# Main.net
KiCad netlist of a schematic drawn in Altium Designer
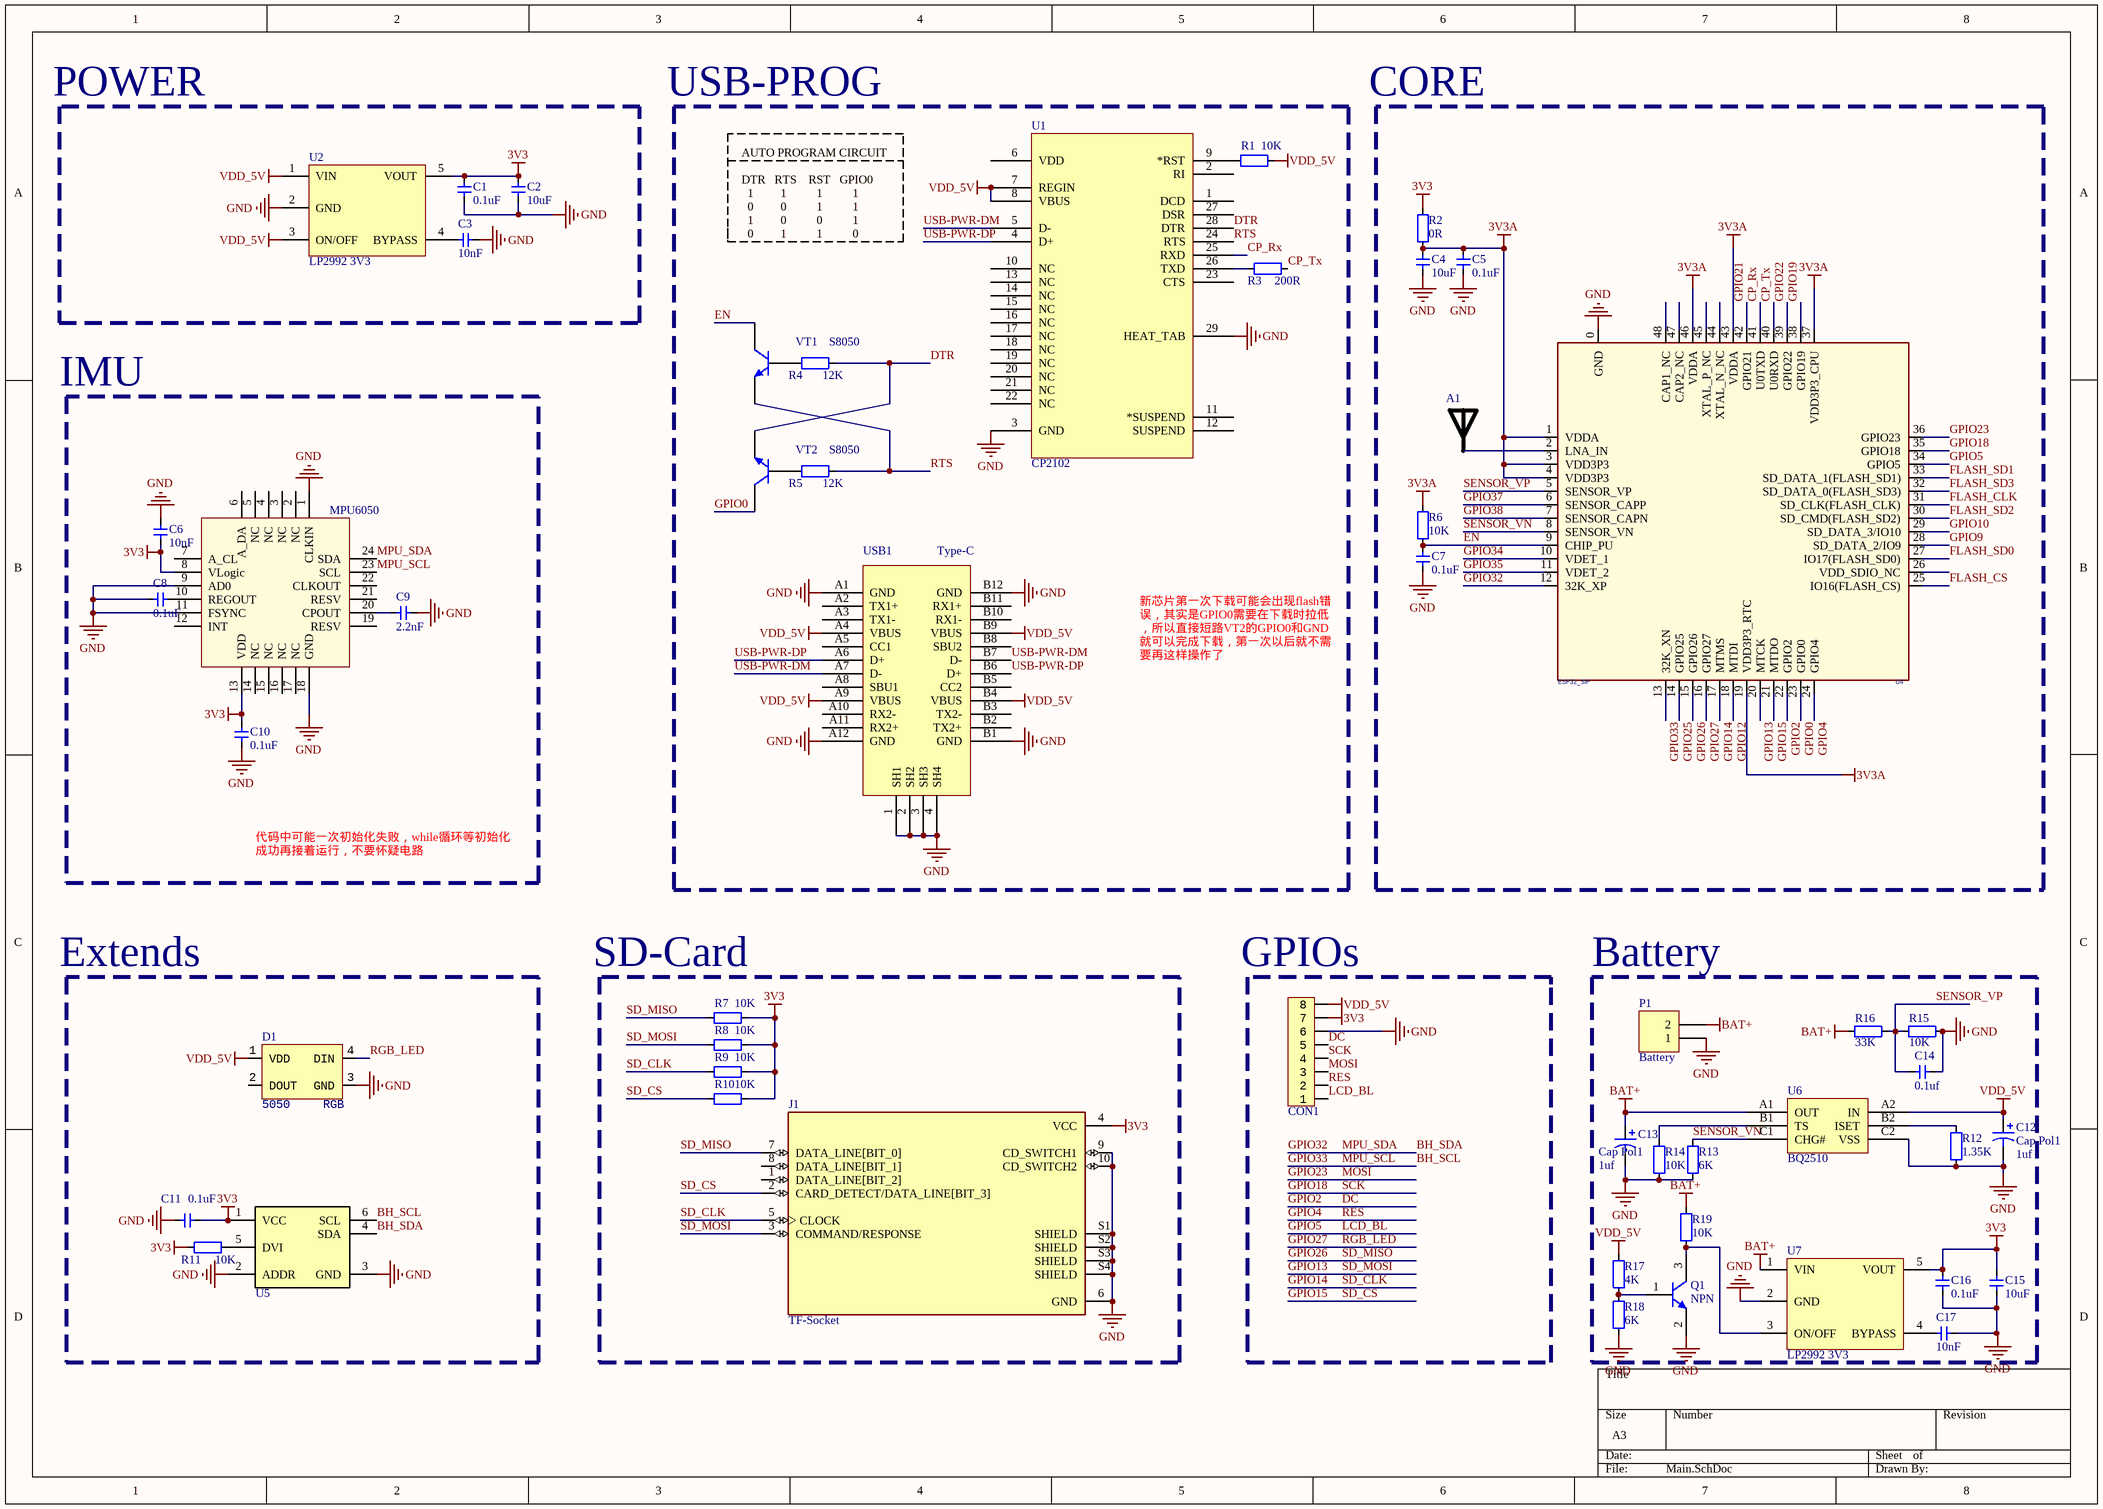
[diagram p0: Main.SchDoc]

(export (version "E")
  (design (tool "Eeschema 10.0.6"))
  (components
    (comp (ref "A1")
      (value "RAINSUN")
      (footprint "ANT-Rainsun-AN5120")
      (libsource (lib "MyPcbLib") (part "ANT-Rainsun-AP5120"))
    )
    (comp (ref "C1")
      (value "0.1uF")
      (footprint "CAP_0402")
      (description "Capacitor")
      (libsource (lib "MyPcbLib") (part "电容-0402"))
    )
    (comp (ref "C2")
      (value "10uF")
      (footprint "CAP_0402")
      (description "Capacitor")
      (libsource (lib "MyPcbLib") (part "电容-0402"))
    )
    (comp (ref "C3")
      (value "10nF")
      (footprint "CAP_0402")
      (description "Capacitor")
      (libsource (lib "MyPcbLib") (part "电容-0402"))
    )
    (comp (ref "C4")
      (value "10uF")
      (footprint "CAP_0402")
      (description "Capacitor")
      (libsource (lib "MyPcbLib") (part "电容-0402"))
    )
    (comp (ref "C5")
      (value "0.1uF")
      (footprint "CAP_0402")
      (description "Capacitor")
      (libsource (lib "MyPcbLib") (part "电容-0402"))
    )
    (comp (ref "C6")
      (value "10nF")
      (footprint "CAP_0402")
      (description "Capacitor")
      (libsource (lib "MyPcbLib") (part "电容-0402"))
    )
    (comp (ref "C7")
      (value "0.1uF")
      (footprint "CAP_0402")
      (description "Capacitor")
      (libsource (lib "MyPcbLib") (part "电容-0402"))
    )
    (comp (ref "C8")
      (value "0.1uF")
      (footprint "CAP_0402")
      (description "Capacitor")
      (libsource (lib "MyPcbLib") (part "电容-0402"))
    )
    (comp (ref "C9")
      (value "2.2nF")
      (footprint "CAP_0402")
      (description "Capacitor")
      (libsource (lib "MyPcbLib") (part "电容-0402"))
    )
    (comp (ref "C10")
      (value "0.1uF")
      (footprint "CAP_0402")
      (description "Capacitor")
      (libsource (lib "MyPcbLib") (part "电容-0402"))
    )
    (comp (ref "C11")
      (value "0.1uF")
      (footprint "CAP_0402")
      (description "Capacitor")
      (libsource (lib "MyPcbLib") (part "电容-0402"))
    )
    (comp (ref "C12")
      (value "Cap Pol1")
      (footprint "6-0805_L")
      (description "Polarized Capacitor (Radial)")
      (fields (field (name "ALTIUM_VALUE") "1uf") (field (name "PUBLISHER") "Altium Limited"))
      (libsource (lib "Miscellaneous Devices") (part "Cap Pol1"))
    )
    (comp (ref "C13")
      (value "Cap Pol1")
      (footprint "6-0805_L")
      (description "Polarized Capacitor (Radial)")
      (fields (field (name "ALTIUM_VALUE") "1uf") (field (name "PUBLISHER") "Altium Limited"))
      (libsource (lib "Miscellaneous Devices") (part "Cap Pol1"))
    )
    (comp (ref "C14")
      (value "0.1uf")
      (footprint "CAP_0402")
      (description "Capacitor")
      (libsource (lib "MyPcbLib") (part "电容-0402"))
    )
    (comp (ref "C15")
      (value "10uF")
      (footprint "CAP_0402")
      (description "Capacitor")
      (libsource (lib "MyPcbLib") (part "电容-0402"))
    )
    (comp (ref "C16")
      (value "0.1uF")
      (footprint "CAP_0402")
      (description "Capacitor")
      (libsource (lib "MyPcbLib") (part "电容-0402"))
    )
    (comp (ref "C17")
      (value "10nF")
      (footprint "CAP_0402")
      (description "Capacitor")
      (libsource (lib "MyPcbLib") (part "电容-0402"))
    )
    (comp (ref "CON1")
      (value "FFC_0.5_8")
      (footprint "FFC_0.5_8")
      (description "FFC")
      (libsource (lib "KitSprout") (part "FFC_0.5_8"))
    )
    (comp (ref "D1")
      (value "RGB")
      (footprint "LED_5050_WS2812B")
      (description "LED")
      (fields (field (name "TYPE") "5050"))
      (libsource (lib "KitSprout") (part "LED_5050_WS2812B"))
    )
    (comp (ref "J1")
      (value "TF-Socket")
      (footprint "TF-Card-Amphenol with TF")
      (description "10 _8 + 2_ Position Card Connector Secure Digital - microSDâ„¢ Surface Mount, Right Angle Gold")
      (fields (field (name "MP") "1140084168") (field (name "MF") "Amphenol Commercial Products"))
      (libsource (lib "MyPcbLib") (part "TF-Socket"))
    )
    (comp (ref "P1")
      (value "Battery")
      (footprint "C0805")
      (description "Header, 2-Pin")
      (fields (field (name "PUBLISHER") "Altium Limited"))
      (libsource (lib "Miscellaneous Connectors") (part "Header 2"))
    )
    (comp (ref "Q1")
      (value "NPN")
      (footprint "SOT-23_N")
      (description "NPN Bipolar Transistor")
      (fields (field (name "PUBLISHER") "Altium Limited"))
      (libsource (lib "Miscellaneous Devices") (part "NPN"))
    )
    (comp (ref "R1")
      (value "10K")
      (footprint "RES_0402")
      (description "Resistor")
      (libsource (lib "") (part "电阻-0402_1"))
    )
    (comp (ref "R2")
      (value "0R")
      (footprint "RES_0402")
      (description "Resistor")
      (libsource (lib "MyPcbLib") (part "电阻-0402"))
    )
    (comp (ref "R3")
      (value "200R")
      (footprint "RES_0402")
      (description "Resistor")
      (libsource (lib "") (part "电阻-0402_1"))
    )
    (comp (ref "R4")
      (value "12K")
      (footprint "RES_0402")
      (description "Resistor")
      (libsource (lib "") (part "电阻-0402_1"))
    )
    (comp (ref "R5")
      (value "12K")
      (footprint "RES_0402")
      (description "Resistor")
      (libsource (lib "") (part "电阻-0402_1"))
    )
    (comp (ref "R6")
      (value "10K")
      (footprint "RES_0402")
      (description "Resistor")
      (libsource (lib "MyPcbLib") (part "电阻-0402"))
    )
    (comp (ref "R7")
      (value "10K")
      (footprint "RES_0402")
      (description "Resistor")
      (libsource (lib "") (part "电阻-0402_1"))
    )
    (comp (ref "R8")
      (value "10K")
      (footprint "RES_0402")
      (description "Resistor")
      (libsource (lib "") (part "电阻-0402_1"))
    )
    (comp (ref "R9")
      (value "10K")
      (footprint "RES_0402")
      (description "Resistor")
      (libsource (lib "") (part "电阻-0402_1"))
    )
    (comp (ref "R10")
      (value "10K")
      (footprint "RES_0402")
      (description "Resistor")
      (libsource (lib "") (part "电阻-0402_1"))
    )
    (comp (ref "R11")
      (value "10K")
      (footprint "RES_0402")
      (description "Resistor")
      (libsource (lib "") (part "电阻-0402_1"))
    )
    (comp (ref "R12")
      (value "1.35K")
      (footprint "RES_0402")
      (description "Resistor")
      (libsource (lib "MyPcbLib") (part "电阻-0402"))
    )
    (comp (ref "R13")
      (value "6K")
      (footprint "RES_0402")
      (description "Resistor")
      (libsource (lib "MyPcbLib") (part "电阻-0402"))
    )
    (comp (ref "R14")
      (value "10K")
      (footprint "RES_0402")
      (description "Resistor")
      (libsource (lib "MyPcbLib") (part "电阻-0402"))
    )
    (comp (ref "R15")
      (value "10K")
      (footprint "RES_0402")
      (description "Resistor")
      (libsource (lib "") (part "电阻-0402_2"))
    )
    (comp (ref "R16")
      (value "33K")
      (footprint "RES_0402")
      (description "Resistor")
      (libsource (lib "") (part "电阻-0402_2"))
    )
    (comp (ref "R17")
      (value "4K")
      (footprint "RES_0402")
      (description "Resistor")
      (libsource (lib "MyPcbLib") (part "电阻-0402"))
    )
    (comp (ref "R18")
      (value "6K")
      (footprint "RES_0402")
      (description "Resistor")
      (libsource (lib "MyPcbLib") (part "电阻-0402"))
    )
    (comp (ref "R19")
      (value "10K")
      (footprint "RES_0402")
      (description "Resistor")
      (libsource (lib "MyPcbLib") (part "电阻-0402"))
    )
    (comp (ref "U1")
      (value "CP2102")
      (footprint "QFN-28")
      (description "USB转TTL")
      (libsource (lib "mLib") (part "CP2102"))
    )
    (comp (ref "U2")
      (value "LP2992 3V3")
      (footprint "SOT23-5")
      (description "LDO")
      (libsource (lib "MyPcbLib") (part "LP2992"))
    )
    (comp (ref "U3")
      (value "MPU6050")
      (footprint "QFN-24")
      (description "六轴传感器")
      (libsource (lib "mLib") (part "MPU6050"))
    )
    (comp (ref "U4")
      (value "ESP32_SIP")
      (footprint "QFN-48_7X7")
      (libsource (lib "MyPcbLib") (part "ESP32-PICO"))
    )
    (comp (ref "U5")
      (value "BH1750FVI-TR")
      (footprint "BH1750FVI")
      (libsource (lib "MyPcbLib") (part "BH1750FVI-TR"))
    )
    (comp (ref "U6")
      (value "BQ2510")
      (footprint "BQ2510")
      (libsource (lib "Integrated_Library1") (part "BQ2510"))
    )
    (comp (ref "U7")
      (value "LP2992 3V3")
      (footprint "SOT23-5")
      (description "LDO")
      (libsource (lib "MyPcbLib") (part "LP2992"))
    )
    (comp (ref "USB1")
      (value "Type-C")
      (footprint "Type-C-TOP")
      (libsource (lib "MyPcbLib") (part "USB-Type-C-TOP"))
    )
    (comp (ref "VT1")
      (value "S8050")
      (footprint "SMT_TRIODE_NPN")
      (description "Surface mount NPN transistor, package SOT-23")
      (libsource (lib "MyPcbLib") (part "SMT_TRIODE_NPN"))
    )
    (comp (ref "VT2")
      (value "S8050")
      (footprint "SMT_TRIODE_NPN")
      (description "Surface mount NPN transistor, package SOT-23")
      (libsource (lib "MyPcbLib") (part "SMT_TRIODE_NPN"))
    )
  )
  (nets
    (net (code "1") (name "/BH_SCL") (class "Default")
      (node (ref "U3") (pin "23") (pinfunction "SCL_23") (pintype "passive"))
      (node (ref "U4") (pin "13") (pinfunction "32K_XN_13") (pintype "passive"))
      (node (ref "U5") (pin "6") (pinfunction "SCL_6") (pintype "passive"))
    )
    (net (code "2") (name "/BH_SDA") (class "Default")
      (node (ref "U3") (pin "24") (pinfunction "SDA_24") (pintype "passive"))
      (node (ref "U4") (pin "12") (pinfunction "32K_XP_12") (pintype "passive"))
      (node (ref "U5") (pin "4") (pinfunction "SDA_4") (pintype "passive"))
    )
    (net (code "3") (name "/CP_Rx") (class "Default")
      (node (ref "U1") (pin "25") (pinfunction "RXD_25") (pintype "passive"))
      (node (ref "U4") (pin "41") (pinfunction "U0TXD_41") (pintype "power_in"))
    )
    (net (code "4") (name "/CP_Tx") (class "Default")
      (node (ref "R3") (pin "1") (pinfunction "1_1") (pintype "passive"))
      (node (ref "U4") (pin "40") (pinfunction "U0RXD_40") (pintype "power_in"))
    )
    (net (code "5") (name "/DC") (class "Default")
      (node (ref "CON1") (pin "5") (pinfunction "5_5") (pintype "passive"))
      (node (ref "U4") (pin "22") (pinfunction "GPIO2_22") (pintype "passive"))
    )
    (net (code "6") (name "/DTR") (class "Default")
      (node (ref "R4") (pin "1") (pinfunction "1_1") (pintype "passive"))
      (node (ref "U1") (pin "28") (pinfunction "DTR_28") (pintype "passive"))
      (node (ref "VT2") (pin "2") (pinfunction "E_2") (pintype "passive"))
    )
    (net (code "7") (name "/EN") (class "Default")
      (node (ref "C7") (pin "1") (pinfunction "1_1") (pintype "passive"))
      (node (ref "R6") (pin "2") (pinfunction "2_2") (pintype "passive"))
      (node (ref "U4") (pin "9") (pinfunction "CHIP_PU_9") (pintype "passive"))
      (node (ref "VT1") (pin "3") (pinfunction "C_3") (pintype "passive"))
    )
    (net (code "8") (name "/FLASH_CLK") (class "Default")
      (node (ref "U4") (pin "31") (pinfunction "SD_CLK(FLASH_CLK)_31") (pintype "passive"))
    )
    (net (code "9") (name "/FLASH_CS") (class "Default")
      (node (ref "U4") (pin "25") (pinfunction "IO16(FLASH_CS)_25") (pintype "passive"))
    )
    (net (code "10") (name "/FLASH_SD0") (class "Default")
      (node (ref "U4") (pin "27") (pinfunction "IO17(FLASH_SD0)_27") (pintype "passive"))
    )
    (net (code "11") (name "/FLASH_SD1") (class "Default")
      (node (ref "U4") (pin "33") (pinfunction "SD_DATA_1(FLASH_SD1)_33") (pintype "passive"))
    )
    (net (code "12") (name "/FLASH_SD2") (class "Default")
      (node (ref "U4") (pin "30") (pinfunction "SD_CMD(FLASH_SD2)_30") (pintype "passive"))
    )
    (net (code "13") (name "/FLASH_SD3") (class "Default")
      (node (ref "U4") (pin "32") (pinfunction "SD_DATA_0(FLASH_SD3)_32") (pintype "passive"))
    )
    (net (code "14") (name "/GPIO0") (class "Default")
      (node (ref "U4") (pin "23") (pinfunction "GPIO0_23") (pintype "passive"))
      (node (ref "VT2") (pin "3") (pinfunction "C_3") (pintype "passive"))
    )
    (net (code "15") (name "/GPIO4") (class "Default")
      (node (ref "CON1") (pin "2") (pinfunction "2_2") (pintype "passive"))
      (node (ref "U4") (pin "24") (pinfunction "GPIO4_24") (pintype "passive"))
    )
    (net (code "16") (name "/GPIO5") (class "Default")
      (node (ref "CON1") (pin "1") (pinfunction "1_1") (pintype "passive"))
      (node (ref "U4") (pin "34") (pinfunction "GPIO5_34") (pintype "passive"))
    )
    (net (code "17") (name "/GPIO9") (class "Default")
      (node (ref "U4") (pin "28") (pinfunction "SD_DATA_2/IO9_28") (pintype "passive"))
    )
    (net (code "18") (name "/GPIO10") (class "Default")
      (node (ref "U4") (pin "29") (pinfunction "SD_DATA_3/IO10_29") (pintype "passive"))
    )
    (net (code "19") (name "/GPIO12") (class "Default")
      (node (ref "U4") (pin "18") (pinfunction "MTDI_18") (pintype "passive"))
    )
    (net (code "20") (name "/GPIO13") (class "Default")
      (node (ref "J1") (pin "3") (pinfunction "COMMAND/RESPONSE_3") (pintype "bidirectional"))
      (node (ref "R8") (pin "2") (pinfunction "2_2") (pintype "passive"))
      (node (ref "U4") (pin "20") (pinfunction "MTCK_20") (pintype "passive"))
    )
    (net (code "21") (name "/GPIO14") (class "Default")
      (node (ref "J1") (pin "5") (pinfunction "CLOCK_5") (pintype "bidirectional"))
      (node (ref "R9") (pin "2") (pinfunction "2_2") (pintype "passive"))
      (node (ref "U4") (pin "17") (pinfunction "MTMS_17") (pintype "passive"))
    )
    (net (code "22") (name "/GPIO15") (class "Default")
      (node (ref "J1") (pin "2") (pinfunction "CARD_DETECT/DATA_LINE[BIT_3]_2") (pintype "bidirectional"))
      (node (ref "R10") (pin "2") (pinfunction "2_2") (pintype "passive"))
      (node (ref "U4") (pin "21") (pinfunction "MTDO_21") (pintype "passive"))
    )
    (net (code "23") (name "/GPIO18") (class "Default")
      (node (ref "CON1") (pin "4") (pinfunction "4_4") (pintype "passive"))
      (node (ref "U4") (pin "35") (pinfunction "GPIO18_35") (pintype "passive"))
    )
    (net (code "24") (name "/GPIO19") (class "Default")
      (node (ref "U4") (pin "38") (pinfunction "GPIO19_38") (pintype "passive"))
    )
    (net (code "25") (name "/GPIO21") (class "Default")
      (node (ref "U4") (pin "42") (pinfunction "GPIO21_42") (pintype "passive"))
    )
    (net (code "26") (name "/GPIO22") (class "Default")
      (node (ref "U4") (pin "39") (pinfunction "GPIO22_39") (pintype "passive"))
    )
    (net (code "27") (name "/GPIO23") (class "Default")
      (node (ref "CON1") (pin "3") (pinfunction "3_3") (pintype "passive"))
      (node (ref "U4") (pin "36") (pinfunction "GPIO23_36") (pintype "passive"))
    )
    (net (code "28") (name "/GPIO25") (class "Default")
      (node (ref "U4") (pin "14") (pinfunction "GPIO25_14") (pintype "passive"))
    )
    (net (code "29") (name "/GPIO26") (class "Default")
      (node (ref "J1") (pin "7") (pinfunction "DATA_LINE[BIT_0]_7") (pintype "bidirectional"))
      (node (ref "R7") (pin "2") (pinfunction "2_2") (pintype "passive"))
      (node (ref "U4") (pin "15") (pinfunction "GPIO26_15") (pintype "passive"))
    )
    (net (code "30") (name "/GPIO27") (class "Default")
      (node (ref "D1") (pin "4") (pinfunction "DIN_4") (pintype "passive"))
      (node (ref "U4") (pin "16") (pinfunction "GPIO27_16") (pintype "passive"))
    )
    (net (code "31") (name "/GPIO34") (class "Default")
      (node (ref "U4") (pin "10") (pinfunction "VDET_1_10") (pintype "passive"))
    )
    (net (code "32") (name "/GPIO35") (class "Default")
      (node (ref "U4") (pin "11") (pinfunction "VDET_2_11") (pintype "passive"))
    )
    (net (code "33") (name "/GPIO37") (class "Default")
      (node (ref "U4") (pin "6") (pinfunction "SENSOR_CAPP_6") (pintype "passive"))
    )
    (net (code "34") (name "/GPIO38") (class "Default")
      (node (ref "U4") (pin "7") (pinfunction "SENSOR_CAPN_7") (pintype "passive"))
    )
    (net (code "35") (name "/RTS") (class "Default")
      (node (ref "R5") (pin "1") (pinfunction "1_1") (pintype "passive"))
      (node (ref "U1") (pin "24") (pinfunction "RTS_24") (pintype "passive"))
      (node (ref "VT1") (pin "2") (pinfunction "E_2") (pintype "passive"))
    )
    (net (code "36") (name "/SENSOR_VN") (class "Default")
      (node (ref "R13") (pin "1") (pinfunction "1_1") (pintype "passive"))
      (node (ref "U4") (pin "8") (pinfunction "SENSOR_VN_8") (pintype "passive"))
      (node (ref "U6") (pin "C1") (pinfunction "CHG#_C1") (pintype "passive"))
    )
    (net (code "37") (name "/SENSOR_VP") (class "Default")
      (node (ref "C14") (pin "2") (pinfunction "2_2") (pintype "passive"))
      (node (ref "R15") (pin "1") (pinfunction "1_1") (pintype "passive"))
      (node (ref "R16") (pin "2") (pinfunction "2_2") (pintype "passive"))
      (node (ref "U4") (pin "5") (pinfunction "SENSOR_VP_5") (pintype "passive"))
    )
    (net (code "38") (name "/USB-PWR-DM") (class "Default")
      (node (ref "U1") (pin "5") (pinfunction "D-_5") (pintype "passive"))
      (node (ref "USB1") (pin "A7") (pinfunction "D-_A7") (pintype "passive"))
      (node (ref "USB1") (pin "B7") (pinfunction "D-_B7") (pintype "passive"))
    )
    (net (code "39") (name "/USB-PWR-DP") (class "Default")
      (node (ref "U1") (pin "4") (pinfunction "D+_4") (pintype "passive"))
      (node (ref "USB1") (pin "A6") (pinfunction "D+_A6") (pintype "passive"))
      (node (ref "USB1") (pin "B6") (pinfunction "D+_B6") (pintype "passive"))
    )
    (net (code "40") (name "3V3") (class "Default")
      (node (ref "C1") (pin "2") (pinfunction "2_2") (pintype "passive"))
      (node (ref "C10") (pin "2") (pinfunction "2_2") (pintype "passive"))
      (node (ref "C11") (pin "1") (pinfunction "1_1") (pintype "passive"))
      (node (ref "C15") (pin "2") (pinfunction "2_2") (pintype "passive"))
      (node (ref "C16") (pin "2") (pinfunction "2_2") (pintype "passive"))
      (node (ref "C2") (pin "2") (pinfunction "2_2") (pintype "passive"))
      (node (ref "C6") (pin "1") (pinfunction "1_1") (pintype "passive"))
      (node (ref "CON1") (pin "7") (pinfunction "7_7") (pintype "passive"))
      (node (ref "J1") (pin "4") (pinfunction "VCC_4") (pintype "power_in"))
      (node (ref "R10") (pin "1") (pinfunction "1_1") (pintype "passive"))
      (node (ref "R11") (pin "2") (pinfunction "2_2") (pintype "passive"))
      (node (ref "R2") (pin "1") (pinfunction "1_1") (pintype "passive"))
      (node (ref "R7") (pin "1") (pinfunction "1_1") (pintype "passive"))
      (node (ref "R8") (pin "1") (pinfunction "1_1") (pintype "passive"))
      (node (ref "R9") (pin "1") (pinfunction "1_1") (pintype "passive"))
      (node (ref "U2") (pin "5") (pinfunction "VOUT_5") (pintype "passive"))
      (node (ref "U3") (pin "13") (pinfunction "VDD_13") (pintype "passive"))
      (node (ref "U3") (pin "8") (pinfunction "VLogic_8") (pintype "passive"))
      (node (ref "U5") (pin "1") (pinfunction "VCC_1") (pintype "passive"))
      (node (ref "U7") (pin "5") (pinfunction "VOUT_5") (pintype "passive"))
    )
    (net (code "41") (name "3V3A") (class "Default")
      (node (ref "C4") (pin "2") (pinfunction "2_2") (pintype "passive"))
      (node (ref "C5") (pin "2") (pinfunction "2_2") (pintype "passive"))
      (node (ref "R2") (pin "2") (pinfunction "2_2") (pintype "passive"))
      (node (ref "R6") (pin "1") (pinfunction "1_1") (pintype "passive"))
      (node (ref "U4") (pin "1") (pinfunction "VDDA_1") (pintype "power_in"))
      (node (ref "U4") (pin "19") (pinfunction "VDD3P3_RTC_19") (pintype "power_in"))
      (node (ref "U4") (pin "3") (pinfunction "VDD3P3_3") (pintype "power_in"))
      (node (ref "U4") (pin "37") (pinfunction "VDD3P3_CPU_37") (pintype "power_in"))
      (node (ref "U4") (pin "4") (pinfunction "VDD3P3_4") (pintype "power_in"))
      (node (ref "U4") (pin "43") (pinfunction "VDDA_43") (pintype "power_in"))
      (node (ref "U4") (pin "46") (pinfunction "VDDA_46") (pintype "power_in"))
    )
    (net (code "42") (name "BAT+") (class "Default")
      (node (ref "C13") (pin "1") (pinfunction "1_1") (pintype "passive"))
      (node (ref "P1") (pin "2") (pinfunction "2_2") (pintype "passive"))
      (node (ref "R16") (pin "1") (pinfunction "1_1") (pintype "passive"))
      (node (ref "R19") (pin "1") (pinfunction "1_1") (pintype "passive"))
      (node (ref "U6") (pin "A1") (pinfunction "OUT_A1") (pintype "passive"))
      (node (ref "U7") (pin "1") (pinfunction "VIN_1") (pintype "passive"))
    )
    (net (code "43") (name "GND") (class "Default")
      (node (ref "C1") (pin "1") (pinfunction "1_1") (pintype "passive"))
      (node (ref "C10") (pin "1") (pinfunction "1_1") (pintype "passive"))
      (node (ref "C11") (pin "2") (pinfunction "2_2") (pintype "passive"))
      (node (ref "C12") (pin "2") (pinfunction "2_2") (pintype "passive"))
      (node (ref "C13") (pin "2") (pinfunction "2_2") (pintype "passive"))
      (node (ref "C14") (pin "1") (pinfunction "1_1") (pintype "passive"))
      (node (ref "C15") (pin "1") (pinfunction "1_1") (pintype "passive"))
      (node (ref "C16") (pin "1") (pinfunction "1_1") (pintype "passive"))
      (node (ref "C17") (pin "1") (pinfunction "1_1") (pintype "passive"))
      (node (ref "C2") (pin "1") (pinfunction "1_1") (pintype "passive"))
      (node (ref "C3") (pin "1") (pinfunction "1_1") (pintype "passive"))
      (node (ref "C4") (pin "1") (pinfunction "1_1") (pintype "passive"))
      (node (ref "C5") (pin "1") (pinfunction "1_1") (pintype "passive"))
      (node (ref "C6") (pin "2") (pinfunction "2_2") (pintype "passive"))
      (node (ref "C7") (pin "2") (pinfunction "2_2") (pintype "passive"))
      (node (ref "C8") (pin "2") (pinfunction "2_2") (pintype "passive"))
      (node (ref "C9") (pin "1") (pinfunction "1_1") (pintype "passive"))
      (node (ref "CON1") (pin "6") (pinfunction "6_6") (pintype "passive"))
      (node (ref "D1") (pin "3") (pinfunction "GND_3") (pintype "passive"))
      (node (ref "J1") (pin "10") (pinfunction "CD_SWITCH2_10") (pintype "bidirectional"))
      (node (ref "J1") (pin "6") (pinfunction "GND_6") (pintype "power_in"))
      (node (ref "J1") (pin "9") (pinfunction "CD_SWITCH1_9") (pintype "bidirectional"))
      (node (ref "J1") (pin "S1") (pinfunction "SHIELD_S1") (pintype "passive"))
      (node (ref "J1") (pin "S2") (pinfunction "SHIELD_S2") (pintype "passive"))
      (node (ref "J1") (pin "S3") (pinfunction "SHIELD_S3") (pintype "passive"))
      (node (ref "J1") (pin "S4") (pinfunction "SHIELD_S4") (pintype "passive"))
      (node (ref "P1") (pin "1") (pinfunction "1_1") (pintype "passive"))
      (node (ref "Q1") (pin "2") (pinfunction "E_2") (pintype "passive"))
      (node (ref "R12") (pin "2") (pinfunction "2_2") (pintype "passive"))
      (node (ref "R13") (pin "2") (pinfunction "2_2") (pintype "passive"))
      (node (ref "R14") (pin "2") (pinfunction "2_2") (pintype "passive"))
      (node (ref "R15") (pin "2") (pinfunction "2_2") (pintype "passive"))
      (node (ref "R18") (pin "2") (pinfunction "2_2") (pintype "passive"))
      (node (ref "U1") (pin "29") (pinfunction "HEAT_TAB_29") (pintype "passive"))
      (node (ref "U1") (pin "3") (pinfunction "GND_3") (pintype "passive"))
      (node (ref "U2") (pin "2") (pinfunction "GND_2") (pintype "passive"))
      (node (ref "U3") (pin "1") (pinfunction "CLKIN_1") (pintype "passive"))
      (node (ref "U3") (pin "11") (pinfunction "FSYNC_11") (pintype "passive"))
      (node (ref "U3") (pin "18") (pinfunction "GND_18") (pintype "passive"))
      (node (ref "U3") (pin "9") (pinfunction "AD0_9") (pintype "passive"))
      (node (ref "U4") (pin "0") (pinfunction "GND_0") (pintype "power_in"))
      (node (ref "U5") (pin "2") (pinfunction "ADDR_2") (pintype "passive"))
      (node (ref "U5") (pin "3") (pinfunction "GND_3") (pintype "passive"))
      (node (ref "U6") (pin "C2") (pinfunction "VSS_C2") (pintype "passive"))
      (node (ref "U7") (pin "2") (pinfunction "GND_2") (pintype "passive"))
      (node (ref "USB1") (pin "1") (pinfunction "SH1_1") (pintype "passive"))
      (node (ref "USB1") (pin "2") (pinfunction "SH2_2") (pintype "passive"))
      (node (ref "USB1") (pin "3") (pinfunction "SH3_3") (pintype "passive"))
      (node (ref "USB1") (pin "4") (pinfunction "SH4_4") (pintype "passive"))
      (node (ref "USB1") (pin "A1") (pinfunction "GND_A1") (pintype "passive"))
      (node (ref "USB1") (pin "A12") (pinfunction "GND_A12") (pintype "passive"))
      (node (ref "USB1") (pin "B1") (pinfunction "GND_B1") (pintype "passive"))
      (node (ref "USB1") (pin "B12") (pinfunction "GND_B12") (pintype "passive"))
    )
    (net (code "44") (name "Net-(Q1-B)") (class "Default")
      (node (ref "Q1") (pin "1") (pinfunction "B_1") (pintype "passive"))
      (node (ref "R17") (pin "2") (pinfunction "2_2") (pintype "passive"))
      (node (ref "R18") (pin "1") (pinfunction "1_1") (pintype "passive"))
    )
    (net (code "45") (name "Net-(Q1-C)") (class "Default")
      (node (ref "Q1") (pin "3") (pinfunction "C_3") (pintype "passive"))
      (node (ref "R19") (pin "2") (pinfunction "2_2") (pintype "passive"))
      (node (ref "U7") (pin "3") (pinfunction "ON/OFF_3") (pintype "passive"))
    )
    (net (code "46") (name "Net-(U1-*RST)") (class "Default")
      (node (ref "R1") (pin "2") (pinfunction "2_2") (pintype "passive"))
      (node (ref "U1") (pin "9") (pinfunction "*RST_9") (pintype "passive"))
    )
    (net (code "47") (name "Net-(U1-TXD)") (class "Default")
      (node (ref "R3") (pin "2") (pinfunction "2_2") (pintype "passive"))
      (node (ref "U1") (pin "26") (pinfunction "TXD_26") (pintype "passive"))
    )
    (net (code "48") (name "Net-(U2-BYPASS)") (class "Default")
      (node (ref "C3") (pin "2") (pinfunction "2_2") (pintype "passive"))
      (node (ref "U2") (pin "4") (pinfunction "BYPASS_4") (pintype "passive"))
    )
    (net (code "49") (name "Net-(U3-CPOUT)") (class "Default")
      (node (ref "C9") (pin "2") (pinfunction "2_2") (pintype "passive"))
      (node (ref "U3") (pin "20") (pinfunction "CPOUT_20") (pintype "passive"))
    )
    (net (code "50") (name "Net-(U3-REGOUT)") (class "Default")
      (node (ref "C8") (pin "1") (pinfunction "1_1") (pintype "passive"))
      (node (ref "U3") (pin "10") (pinfunction "REGOUT_10") (pintype "passive"))
    )
    (net (code "51") (name "Net-(U4-LNA_IN)") (class "Default")
      (node (ref "A1") (pin "1") (pinfunction "1_1") (pintype "passive"))
      (node (ref "U4") (pin "2") (pinfunction "LNA_IN_2") (pintype "passive"))
    )
    (net (code "52") (name "Net-(U5-DVI)") (class "Default")
      (node (ref "R11") (pin "1") (pinfunction "1_1") (pintype "passive"))
      (node (ref "U5") (pin "5") (pinfunction "DVI_5") (pintype "passive"))
    )
    (net (code "53") (name "Net-(U6-ISET)") (class "Default")
      (node (ref "R12") (pin "1") (pinfunction "1_1") (pintype "passive"))
      (node (ref "U6") (pin "B2") (pinfunction "ISET_B2") (pintype "passive"))
    )
    (net (code "54") (name "Net-(U6-TS)") (class "Default")
      (node (ref "R14") (pin "1") (pinfunction "1_1") (pintype "passive"))
      (node (ref "U6") (pin "B1") (pinfunction "TS_B1") (pintype "passive"))
    )
    (net (code "55") (name "Net-(U7-BYPASS)") (class "Default")
      (node (ref "C17") (pin "2") (pinfunction "2_2") (pintype "passive"))
      (node (ref "U7") (pin "4") (pinfunction "BYPASS_4") (pintype "passive"))
    )
    (net (code "56") (name "Net-(VT1-B)") (class "Default")
      (node (ref "R4") (pin "2") (pinfunction "2_2") (pintype "passive"))
      (node (ref "VT1") (pin "1") (pinfunction "B_1") (pintype "passive"))
    )
    (net (code "57") (name "Net-(VT2-B)") (class "Default")
      (node (ref "R5") (pin "2") (pinfunction "2_2") (pintype "passive"))
      (node (ref "VT2") (pin "1") (pinfunction "B_1") (pintype "passive"))
    )
    (net (code "58") (name "VDD_5V") (class "Default")
      (node (ref "C12") (pin "1") (pinfunction "1_1") (pintype "passive"))
      (node (ref "CON1") (pin "8") (pinfunction "8_8") (pintype "passive"))
      (node (ref "D1") (pin "1") (pinfunction "VDD_1") (pintype "passive"))
      (node (ref "R1") (pin "1") (pinfunction "1_1") (pintype "passive"))
      (node (ref "R17") (pin "1") (pinfunction "1_1") (pintype "passive"))
      (node (ref "U1") (pin "7") (pinfunction "REGIN_7") (pintype "passive"))
      (node (ref "U1") (pin "8") (pinfunction "VBUS_8") (pintype "passive"))
      (node (ref "U2") (pin "1") (pinfunction "VIN_1") (pintype "passive"))
      (node (ref "U2") (pin "3") (pinfunction "ON/OFF_3") (pintype "passive"))
      (node (ref "U6") (pin "A2") (pinfunction "IN_A2") (pintype "passive"))
      (node (ref "USB1") (pin "A4") (pinfunction "VBUS_A4") (pintype "passive"))
      (node (ref "USB1") (pin "A9") (pinfunction "VBUS_A9") (pintype "passive"))
      (node (ref "USB1") (pin "B4") (pinfunction "VBUS_B4") (pintype "passive"))
      (node (ref "USB1") (pin "B9") (pinfunction "VBUS_B9") (pintype "passive"))
    )
    (net (code "59") (name "unconnected-(D1-DOUT-Pad2)") (class "Default")
      (node (ref "D1") (pin "2") (pinfunction "DOUT_2") (pintype "passive"))
    )
    (net (code "60") (name "unconnected-(J1-DATA_LINE[BIT_1]-Pad8)") (class "Default")
      (node (ref "J1") (pin "8") (pinfunction "DATA_LINE[BIT_1]_8") (pintype "bidirectional"))
    )
    (net (code "61") (name "unconnected-(J1-DATA_LINE[BIT_2]-Pad1)") (class "Default")
      (node (ref "J1") (pin "1") (pinfunction "DATA_LINE[BIT_2]_1") (pintype "bidirectional"))
    )
    (net (code "62") (name "unconnected-(U1-*SUSPEND-Pad11)") (class "Default")
      (node (ref "U1") (pin "11") (pinfunction "*SUSPEND_11") (pintype "passive"))
    )
    (net (code "63") (name "unconnected-(U1-CTS-Pad23)") (class "Default")
      (node (ref "U1") (pin "23") (pinfunction "CTS_23") (pintype "passive"))
    )
    (net (code "64") (name "unconnected-(U1-DCD-Pad1)") (class "Default")
      (node (ref "U1") (pin "1") (pinfunction "DCD_1") (pintype "passive"))
    )
    (net (code "65") (name "unconnected-(U1-DSR-Pad27)") (class "Default")
      (node (ref "U1") (pin "27") (pinfunction "DSR_27") (pintype "passive"))
    )
    (net (code "66") (name "unconnected-(U1-NC-Pad10)") (class "Default")
      (node (ref "U1") (pin "10") (pinfunction "NC_10") (pintype "passive"))
    )
    (net (code "67") (name "unconnected-(U1-NC-Pad13)") (class "Default")
      (node (ref "U1") (pin "13") (pinfunction "NC_13") (pintype "passive"))
    )
    (net (code "68") (name "unconnected-(U1-NC-Pad14)") (class "Default")
      (node (ref "U1") (pin "14") (pinfunction "NC_14") (pintype "passive"))
    )
    (net (code "69") (name "unconnected-(U1-NC-Pad15)") (class "Default")
      (node (ref "U1") (pin "15") (pinfunction "NC_15") (pintype "passive"))
    )
    (net (code "70") (name "unconnected-(U1-NC-Pad16)") (class "Default")
      (node (ref "U1") (pin "16") (pinfunction "NC_16") (pintype "passive"))
    )
    (net (code "71") (name "unconnected-(U1-NC-Pad17)") (class "Default")
      (node (ref "U1") (pin "17") (pinfunction "NC_17") (pintype "passive"))
    )
    (net (code "72") (name "unconnected-(U1-NC-Pad18)") (class "Default")
      (node (ref "U1") (pin "18") (pinfunction "NC_18") (pintype "passive"))
    )
    (net (code "73") (name "unconnected-(U1-NC-Pad19)") (class "Default")
      (node (ref "U1") (pin "19") (pinfunction "NC_19") (pintype "passive"))
    )
    (net (code "74") (name "unconnected-(U1-NC-Pad20)") (class "Default")
      (node (ref "U1") (pin "20") (pinfunction "NC_20") (pintype "passive"))
    )
    (net (code "75") (name "unconnected-(U1-NC-Pad21)") (class "Default")
      (node (ref "U1") (pin "21") (pinfunction "NC_21") (pintype "passive"))
    )
    (net (code "76") (name "unconnected-(U1-NC-Pad22)") (class "Default")
      (node (ref "U1") (pin "22") (pinfunction "NC_22") (pintype "passive"))
    )
    (net (code "77") (name "unconnected-(U1-RI-Pad2)") (class "Default")
      (node (ref "U1") (pin "2") (pinfunction "RI_2") (pintype "passive"))
    )
    (net (code "78") (name "unconnected-(U1-SUSPEND-Pad12)") (class "Default")
      (node (ref "U1") (pin "12") (pinfunction "SUSPEND_12") (pintype "passive"))
    )
    (net (code "79") (name "unconnected-(U1-VDD-Pad6)") (class "Default")
      (node (ref "U1") (pin "6") (pinfunction "VDD_6") (pintype "passive"))
    )
    (net (code "80") (name "unconnected-(U3-A_CL-Pad7)") (class "Default")
      (node (ref "U3") (pin "7") (pinfunction "A_CL_7") (pintype "passive"))
    )
    (net (code "81") (name "unconnected-(U3-A_DA-Pad6)") (class "Default")
      (node (ref "U3") (pin "6") (pinfunction "A_DA_6") (pintype "passive"))
    )
    (net (code "82") (name "unconnected-(U3-CLKOUT-Pad22)") (class "Default")
      (node (ref "U3") (pin "22") (pinfunction "CLKOUT_22") (pintype "passive"))
    )
    (net (code "83") (name "unconnected-(U3-INT-Pad12)") (class "Default")
      (node (ref "U3") (pin "12") (pinfunction "INT_12") (pintype "passive"))
    )
    (net (code "84") (name "unconnected-(U3-NC-Pad2)") (class "Default")
      (node (ref "U3") (pin "2") (pinfunction "NC_2") (pintype "passive"))
    )
    (net (code "85") (name "unconnected-(U3-NC-Pad3)") (class "Default")
      (node (ref "U3") (pin "3") (pinfunction "NC_3") (pintype "passive"))
    )
    (net (code "86") (name "unconnected-(U3-NC-Pad4)") (class "Default")
      (node (ref "U3") (pin "4") (pinfunction "NC_4") (pintype "passive"))
    )
    (net (code "87") (name "unconnected-(U3-NC-Pad5)") (class "Default")
      (node (ref "U3") (pin "5") (pinfunction "NC_5") (pintype "passive"))
    )
    (net (code "88") (name "unconnected-(U3-NC-Pad14)") (class "Default")
      (node (ref "U3") (pin "14") (pinfunction "NC_14") (pintype "passive"))
    )
    (net (code "89") (name "unconnected-(U3-NC-Pad15)") (class "Default")
      (node (ref "U3") (pin "15") (pinfunction "NC_15") (pintype "passive"))
    )
    (net (code "90") (name "unconnected-(U3-NC-Pad16)") (class "Default")
      (node (ref "U3") (pin "16") (pinfunction "NC_16") (pintype "passive"))
    )
    (net (code "91") (name "unconnected-(U3-NC-Pad17)") (class "Default")
      (node (ref "U3") (pin "17") (pinfunction "NC_17") (pintype "passive"))
    )
    (net (code "92") (name "unconnected-(U3-RESV-Pad19)") (class "Default")
      (node (ref "U3") (pin "19") (pinfunction "RESV_19") (pintype "passive"))
    )
    (net (code "93") (name "unconnected-(U3-RESV-Pad21)") (class "Default")
      (node (ref "U3") (pin "21") (pinfunction "RESV_21") (pintype "passive"))
    )
    (net (code "94") (name "unconnected-(U4-CAP1_NC-Pad48)") (class "Default")
      (node (ref "U4") (pin "48") (pinfunction "CAP1_NC_48") (pintype "passive"))
    )
    (net (code "95") (name "unconnected-(U4-CAP2_NC-Pad47)") (class "Default")
      (node (ref "U4") (pin "47") (pinfunction "CAP2_NC_47") (pintype "passive"))
    )
    (net (code "96") (name "unconnected-(U4-VDD_SDIO_NC-Pad26)") (class "Default")
      (node (ref "U4") (pin "26") (pinfunction "VDD_SDIO_NC_26") (pintype "passive"))
    )
    (net (code "97") (name "unconnected-(U4-XTAL_N_NC-Pad44)") (class "Default")
      (node (ref "U4") (pin "44") (pinfunction "XTAL_N_NC_44") (pintype "passive"))
    )
    (net (code "98") (name "unconnected-(U4-XTAL_P_NC-Pad45)") (class "Default")
      (node (ref "U4") (pin "45") (pinfunction "XTAL_P_NC_45") (pintype "passive"))
    )
    (net (code "99") (name "unconnected-(USB1-CC1-PadA5)") (class "Default")
      (node (ref "USB1") (pin "A5") (pinfunction "CC1_A5") (pintype "passive"))
    )
    (net (code "100") (name "unconnected-(USB1-CC2-PadB5)") (class "Default")
      (node (ref "USB1") (pin "B5") (pinfunction "CC2_B5") (pintype "passive"))
    )
    (net (code "101") (name "unconnected-(USB1-RX1+-PadB11)") (class "Default")
      (node (ref "USB1") (pin "B11") (pinfunction "RX1+_B11") (pintype "passive"))
    )
    (net (code "102") (name "unconnected-(USB1-RX1--PadB10)") (class "Default")
      (node (ref "USB1") (pin "B10") (pinfunction "RX1-_B10") (pintype "passive"))
    )
    (net (code "103") (name "unconnected-(USB1-RX2+-PadA11)") (class "Default")
      (node (ref "USB1") (pin "A11") (pinfunction "RX2+_A11") (pintype "passive"))
    )
    (net (code "104") (name "unconnected-(USB1-RX2--PadA10)") (class "Default")
      (node (ref "USB1") (pin "A10") (pinfunction "RX2-_A10") (pintype "passive"))
    )
    (net (code "105") (name "unconnected-(USB1-SBU1-PadA8)") (class "Default")
      (node (ref "USB1") (pin "A8") (pinfunction "SBU1_A8") (pintype "passive"))
    )
    (net (code "106") (name "unconnected-(USB1-SBU2-PadB8)") (class "Default")
      (node (ref "USB1") (pin "B8") (pinfunction "SBU2_B8") (pintype "passive"))
    )
    (net (code "107") (name "unconnected-(USB1-TX1+-PadA2)") (class "Default")
      (node (ref "USB1") (pin "A2") (pinfunction "TX1+_A2") (pintype "passive"))
    )
    (net (code "108") (name "unconnected-(USB1-TX1--PadA3)") (class "Default")
      (node (ref "USB1") (pin "A3") (pinfunction "TX1-_A3") (pintype "passive"))
    )
    (net (code "109") (name "unconnected-(USB1-TX2+-PadB2)") (class "Default")
      (node (ref "USB1") (pin "B2") (pinfunction "TX2+_B2") (pintype "passive"))
    )
    (net (code "110") (name "unconnected-(USB1-TX2--PadB3)") (class "Default")
      (node (ref "USB1") (pin "B3") (pinfunction "TX2-_B3") (pintype "passive"))
    )
  )
)
